# BatteryController.net
KiCad netlist of a schematic drawn in Altium Designer
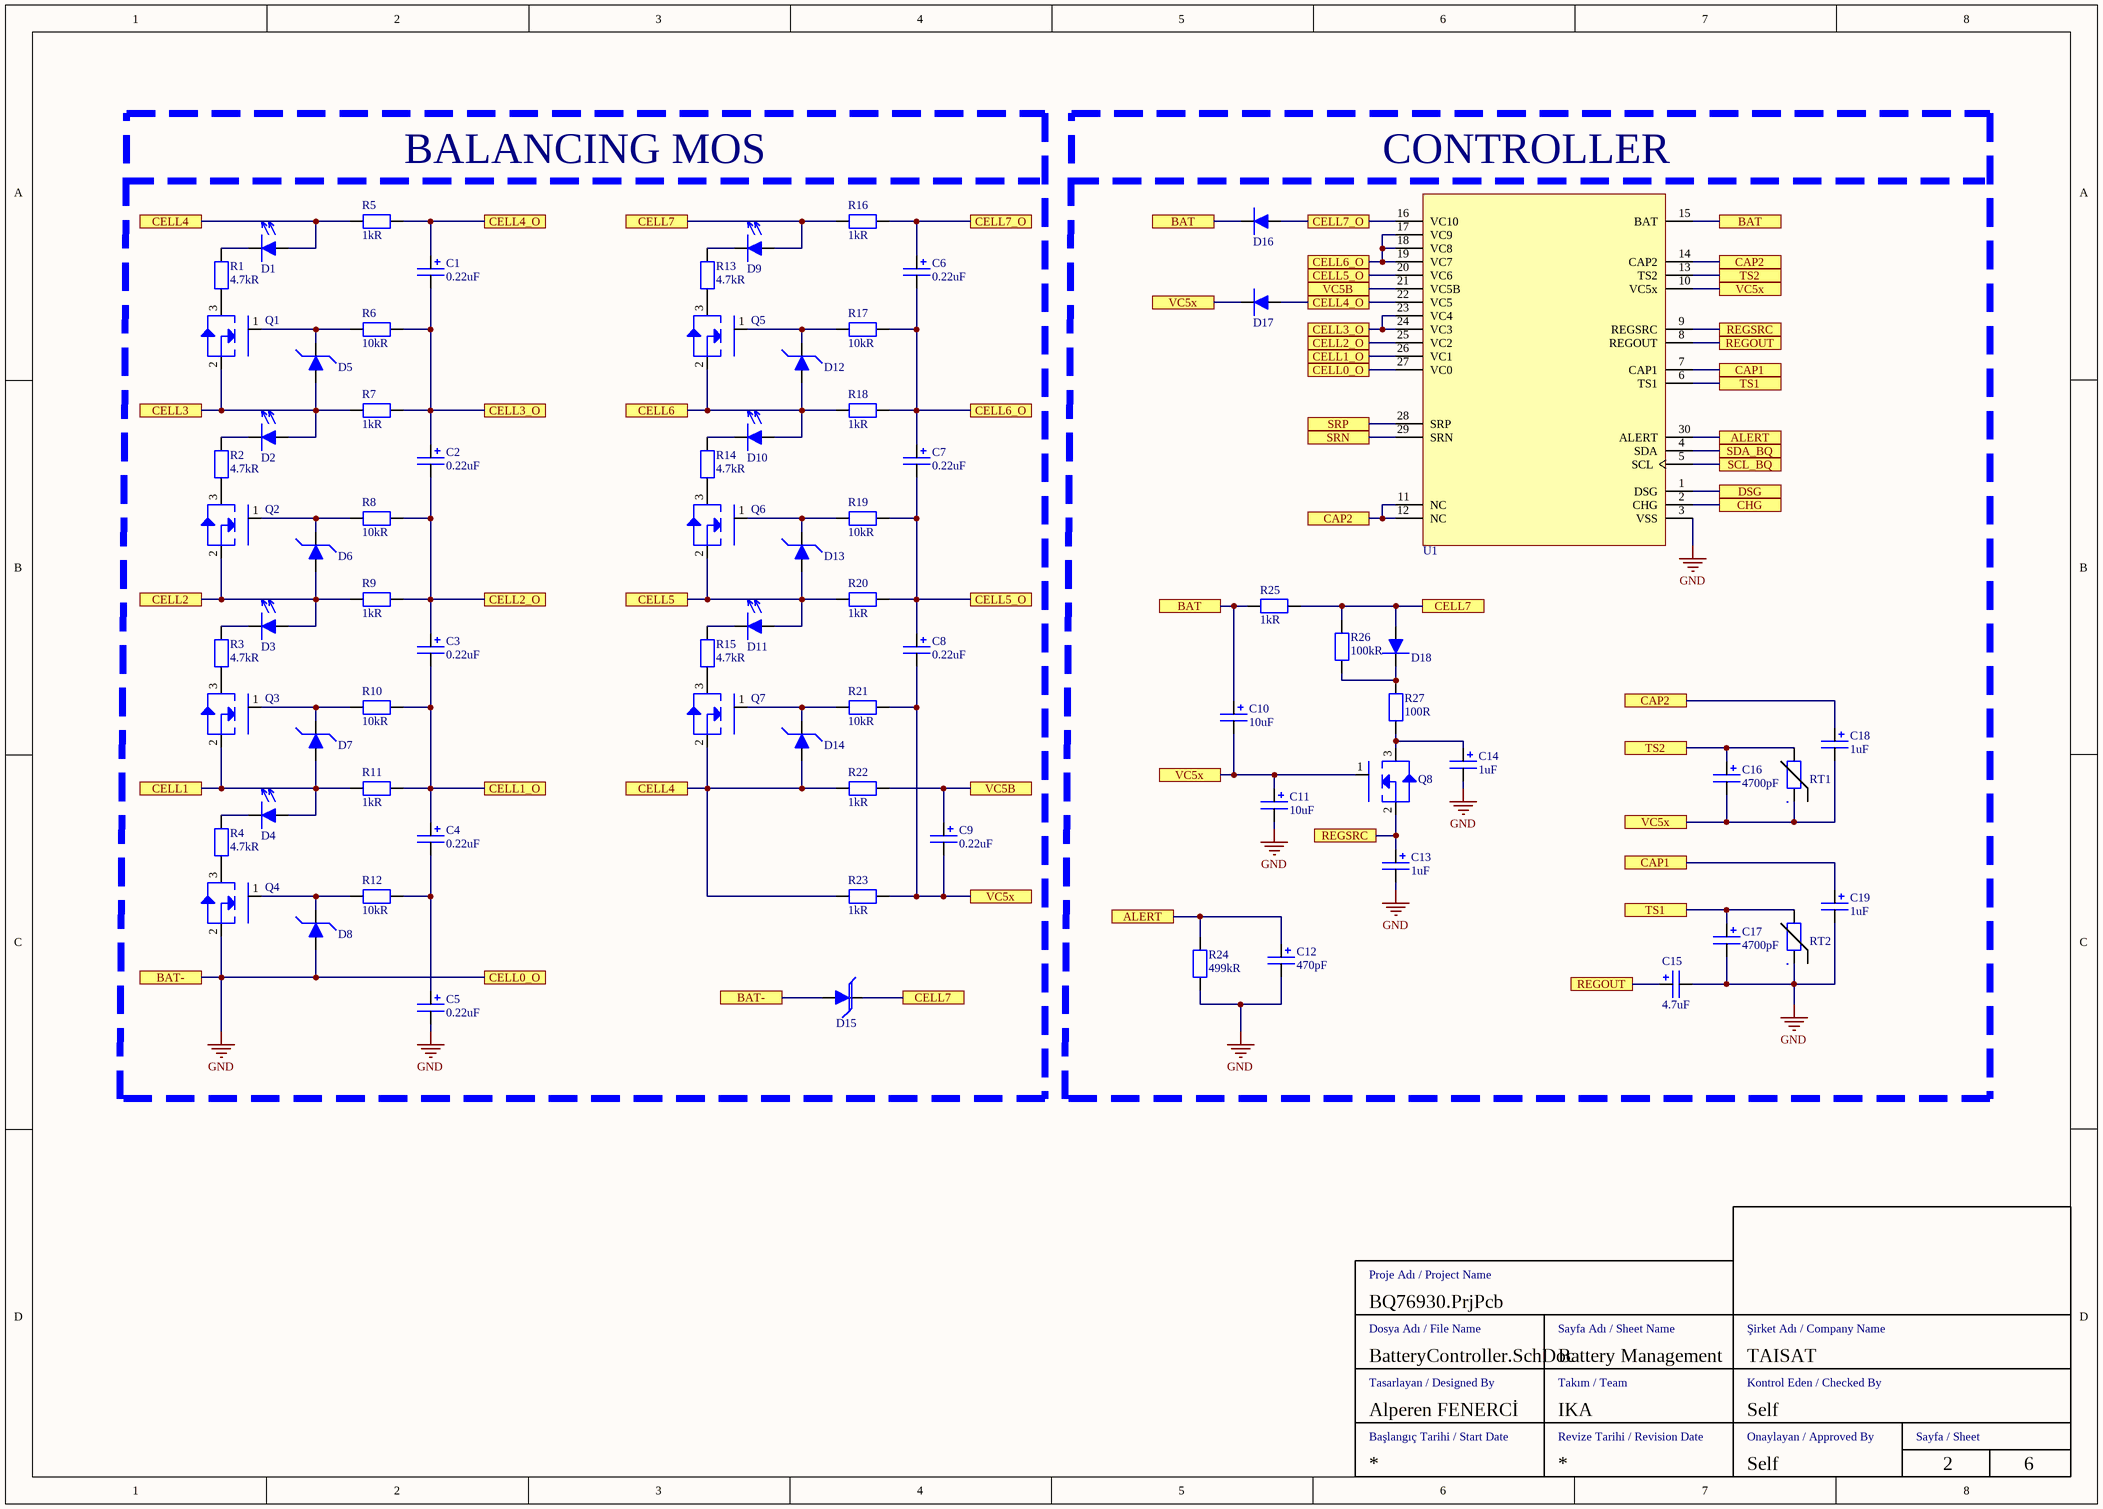
[diagram p0: BatteryController.SchDoc]

(export (version "E")
  (design (tool "Eeschema 10.0.6"))
  (components
    (comp (ref "C1")
      (value "0.22uF")
      (footprint "CAP 0603")
      (description "Multilayer Ceramic Capacitor")
      (fields (field (name "Comment") "CAP 0603"))
      (libsource (lib "Kaptanyums Lib") (part "CAP 0603"))
    )
    (comp (ref "C2")
      (value "0.22uF")
      (footprint "CAP 0603")
      (description "Multilayer Ceramic Capacitor")
      (fields (field (name "Comment") "CAP 0603"))
      (libsource (lib "Kaptanyums Lib") (part "CAP 0603"))
    )
    (comp (ref "C3")
      (value "0.22uF")
      (footprint "CAP 0603")
      (description "Multilayer Ceramic Capacitor")
      (fields (field (name "Comment") "CAP 0603"))
      (libsource (lib "Kaptanyums Lib") (part "CAP 0603"))
    )
    (comp (ref "C4")
      (value "0.22uF")
      (footprint "CAP 0603")
      (description "Multilayer Ceramic Capacitor")
      (fields (field (name "Comment") "CAP 0603"))
      (libsource (lib "Kaptanyums Lib") (part "CAP 0603"))
    )
    (comp (ref "C5")
      (value "0.22uF")
      (footprint "CAP 0603")
      (description "Multilayer Ceramic Capacitor")
      (fields (field (name "Comment") "CAP 0603"))
      (libsource (lib "Kaptanyums Lib") (part "CAP 0603"))
    )
    (comp (ref "C6")
      (value "0.22uF")
      (footprint "CAP 0603")
      (description "Multilayer Ceramic Capacitor")
      (fields (field (name "Comment") "CAP 0603"))
      (libsource (lib "Kaptanyums Lib") (part "CAP 0603"))
    )
    (comp (ref "C7")
      (value "0.22uF")
      (footprint "CAP 0603")
      (description "Multilayer Ceramic Capacitor")
      (fields (field (name "Comment") "CAP 0603"))
      (libsource (lib "Kaptanyums Lib") (part "CAP 0603"))
    )
    (comp (ref "C8")
      (value "0.22uF")
      (footprint "CAP 0603")
      (description "Multilayer Ceramic Capacitor")
      (fields (field (name "Comment") "CAP 0603"))
      (libsource (lib "Kaptanyums Lib") (part "CAP 0603"))
    )
    (comp (ref "C9")
      (value "0.22uF")
      (footprint "CAP 0603")
      (description "Multilayer Ceramic Capacitor")
      (fields (field (name "Comment") "CAP 0603"))
      (libsource (lib "Kaptanyums Lib") (part "CAP 0603"))
    )
    (comp (ref "C10")
      (value "10uF")
      (footprint "CAP 0603")
      (description "Multilayer Ceramic Capacitor")
      (fields (field (name "Comment") "CAP 0603"))
      (libsource (lib "Kaptanyums Lib") (part "CAP 0603"))
    )
    (comp (ref "C11")
      (value "10uF")
      (footprint "CAP 0603")
      (description "Multilayer Ceramic Capacitor")
      (fields (field (name "Comment") "CAP 0603"))
      (libsource (lib "Kaptanyums Lib") (part "CAP 0603"))
    )
    (comp (ref "C12")
      (value "470pF")
      (footprint "CAP 0603")
      (description "Multilayer Ceramic Capacitor")
      (fields (field (name "Comment") "CAP 0603"))
      (libsource (lib "Kaptanyums Lib") (part "CAP 0603"))
    )
    (comp (ref "C13")
      (value "1uF")
      (footprint "CAP 0603")
      (description "Multilayer Ceramic Capacitor")
      (fields (field (name "Comment") "CAP 0603"))
      (libsource (lib "Kaptanyums Lib") (part "CAP 0603"))
    )
    (comp (ref "C14")
      (value "1uF")
      (footprint "CAP 0603")
      (description "Multilayer Ceramic Capacitor")
      (fields (field (name "Comment") "CAP 0603"))
      (libsource (lib "Kaptanyums Lib") (part "CAP 0603"))
    )
    (comp (ref "C15")
      (value "4.7uF")
      (footprint "CAP 0603")
      (description "Multilayer Ceramic Capacitor")
      (fields (field (name "Comment") "CAP 0603"))
      (libsource (lib "Kaptanyums Lib") (part "CAP 0603"))
    )
    (comp (ref "C16")
      (value "4700pF")
      (footprint "CAP 0603")
      (description "Multilayer Ceramic Capacitor")
      (fields (field (name "Comment") "CAP 0603"))
      (libsource (lib "Kaptanyums Lib") (part "CAP 0603"))
    )
    (comp (ref "C17")
      (value "4700pF")
      (footprint "CAP 0603")
      (description "Multilayer Ceramic Capacitor")
      (fields (field (name "Comment") "CAP 0603"))
      (libsource (lib "Kaptanyums Lib") (part "CAP 0603"))
    )
    (comp (ref "C18")
      (value "1uF")
      (footprint "CAP 0603")
      (description "Multilayer Ceramic Capacitor")
      (fields (field (name "Comment") "CAP 0603"))
      (libsource (lib "Kaptanyums Lib") (part "CAP 0603"))
    )
    (comp (ref "C19")
      (value "1uF")
      (footprint "CAP 0603")
      (description "Multilayer Ceramic Capacitor")
      (fields (field (name "Comment") "CAP 0603"))
      (libsource (lib "Kaptanyums Lib") (part "CAP 0603"))
    )
    (comp (ref "D1")
      (value "LTW-C191TLA")
      (footprint "LED 0603")
      (description "Chip LED")
      (libsource (lib "Kaptanyums Lib") (part "LED 0603"))
    )
    (comp (ref "D2")
      (value "LTW-C191TLA")
      (footprint "LED 0603")
      (description "Chip LED")
      (libsource (lib "Kaptanyums Lib") (part "LED 0603"))
    )
    (comp (ref "D3")
      (value "LTW-C191TLA")
      (footprint "LED 0603")
      (description "Chip LED")
      (libsource (lib "Kaptanyums Lib") (part "LED 0603"))
    )
    (comp (ref "D4")
      (value "LTW-C191TLA")
      (footprint "LED 0603")
      (description "Chip LED")
      (libsource (lib "Kaptanyums Lib") (part "LED 0603"))
    )
    (comp (ref "D5")
      (value "MM3Z5V1T1G")
      (footprint "SOD323")
      (description "Diode Zener")
      (fields (field (name "VOLTAGE") "5.1V"))
      (libsource (lib "Kaptanyums Lib") (part "MM3Z5V1T1G"))
    )
    (comp (ref "D6")
      (value "MM3Z5V1T1G")
      (footprint "SOD323")
      (description "Diode Zener")
      (fields (field (name "VOLTAGE") "5.1V"))
      (libsource (lib "Kaptanyums Lib") (part "MM3Z5V1T1G"))
    )
    (comp (ref "D7")
      (value "MM3Z5V1T1G")
      (footprint "SOD323")
      (description "Diode Zener")
      (fields (field (name "VOLTAGE") "5.1V"))
      (libsource (lib "Kaptanyums Lib") (part "MM3Z5V1T1G"))
    )
    (comp (ref "D8")
      (value "MM3Z5V1T1G")
      (footprint "SOD323")
      (description "Diode Zener")
      (fields (field (name "VOLTAGE") "5.1V"))
      (libsource (lib "Kaptanyums Lib") (part "MM3Z5V1T1G"))
    )
    (comp (ref "D9")
      (value "LTW-C191TLA")
      (footprint "LED 0603")
      (description "Chip LED")
      (libsource (lib "Kaptanyums Lib") (part "LED 0603"))
    )
    (comp (ref "D10")
      (value "LTW-C191TLA")
      (footprint "LED 0603")
      (description "Chip LED")
      (libsource (lib "Kaptanyums Lib") (part "LED 0603"))
    )
    (comp (ref "D11")
      (value "LTW-C191TLA")
      (footprint "LED 0603")
      (description "Chip LED")
      (libsource (lib "Kaptanyums Lib") (part "LED 0603"))
    )
    (comp (ref "D12")
      (value "MM3Z5V1T1G")
      (footprint "SOD323")
      (description "Diode Zener")
      (fields (field (name "VOLTAGE") "5.1V"))
      (libsource (lib "Kaptanyums Lib") (part "MM3Z5V1T1G"))
    )
    (comp (ref "D13")
      (value "MM3Z5V1T1G")
      (footprint "SOD323")
      (description "Diode Zener")
      (fields (field (name "VOLTAGE") "5.1V"))
      (libsource (lib "Kaptanyums Lib") (part "MM3Z5V1T1G"))
    )
    (comp (ref "D14")
      (value "MM3Z5V1T1G")
      (footprint "SOD323")
      (description "Diode Zener")
      (fields (field (name "VOLTAGE") "5.1V"))
      (libsource (lib "Kaptanyums Lib") (part "MM3Z5V1T1G"))
    )
    (comp (ref "D15")
      (value "SMAJ36A-HT")
      (footprint "DO214AC")
      (description "Diode TVS")
      (fields (field (name "VOLTAGE") "36V"))
      (libsource (lib "Kaptanyums Lib") (part "SMAJ36A-HT"))
    )
    (comp (ref "D16")
      (value "BAV20W-7-F")
      (footprint "SOD123")
      (description "Diode Switch")
      (fields (field (name "VOLTAGE") "150V"))
      (libsource (lib "Kaptanyums Lib") (part "BAV20W-7-F"))
    )
    (comp (ref "D17")
      (value "BAV20W-7-F")
      (footprint "SOD123")
      (description "Diode Switch")
      (fields (field (name "VOLTAGE") "150V"))
      (libsource (lib "Kaptanyums Lib") (part "BAV20W-7-F"))
    )
    (comp (ref "D18")
      (value "1N4148WS")
      (footprint "SOD323")
      (description "Diode Gen")
      (fields (field (name "VOLTAGE") "75V"))
      (libsource (lib "Kaptanyums Lib") (part "1N4148WS"))
    )
    (comp (ref "Q1")
      (value "2N7002K")
      (footprint "SOT23-3")
      (description "MOSFET")
      (fields (field (name "VOLTAGE") "60V"))
      (libsource (lib "Kaptanyums Lib") (part "2N7002K"))
    )
    (comp (ref "Q2")
      (value "2N7002K")
      (footprint "SOT23-3")
      (description "MOSFET")
      (fields (field (name "VOLTAGE") "60V"))
      (libsource (lib "Kaptanyums Lib") (part "2N7002K"))
    )
    (comp (ref "Q3")
      (value "2N7002K")
      (footprint "SOT23-3")
      (description "MOSFET")
      (fields (field (name "VOLTAGE") "60V"))
      (libsource (lib "Kaptanyums Lib") (part "2N7002K"))
    )
    (comp (ref "Q4")
      (value "2N7002K")
      (footprint "SOT23-3")
      (description "MOSFET")
      (fields (field (name "VOLTAGE") "60V"))
      (libsource (lib "Kaptanyums Lib") (part "2N7002K"))
    )
    (comp (ref "Q5")
      (value "2N7002K")
      (footprint "SOT23-3")
      (description "MOSFET")
      (fields (field (name "VOLTAGE") "60V"))
      (libsource (lib "Kaptanyums Lib") (part "2N7002K"))
    )
    (comp (ref "Q6")
      (value "2N7002K")
      (footprint "SOT23-3")
      (description "MOSFET")
      (fields (field (name "VOLTAGE") "60V"))
      (libsource (lib "Kaptanyums Lib") (part "2N7002K"))
    )
    (comp (ref "Q7")
      (value "2N7002K")
      (footprint "SOT23-3")
      (description "MOSFET")
      (fields (field (name "VOLTAGE") "60V"))
      (libsource (lib "Kaptanyums Lib") (part "2N7002K"))
    )
    (comp (ref "Q8")
      (value "2N7002K")
      (footprint "SOT23-3")
      (description "MOSFET")
      (fields (field (name "VOLTAGE") "60V"))
      (libsource (lib "Kaptanyums Lib") (part "2N7002K"))
    )
    (comp (ref "R1")
      (value "4.7kR")
      (footprint "RESISTOR 1206")
      (description "SMD Chip Resistor")
      (fields (field (name "Comment") "RES 1206"))
      (libsource (lib "Kaptanyums Lib") (part "RES 1206"))
    )
    (comp (ref "R2")
      (value "4.7kR")
      (footprint "RESISTOR 1206")
      (description "SMD Chip Resistor")
      (fields (field (name "Comment") "RES 1206"))
      (libsource (lib "Kaptanyums Lib") (part "RES 1206"))
    )
    (comp (ref "R3")
      (value "4.7kR")
      (footprint "RESISTOR 1206")
      (description "SMD Chip Resistor")
      (fields (field (name "Comment") "RES 1206"))
      (libsource (lib "Kaptanyums Lib") (part "RES 1206"))
    )
    (comp (ref "R4")
      (value "4.7kR")
      (footprint "RESISTOR 1206")
      (description "SMD Chip Resistor")
      (fields (field (name "Comment") "RES 1206"))
      (libsource (lib "Kaptanyums Lib") (part "RES 1206"))
    )
    (comp (ref "R5")
      (value "1kR")
      (footprint "RESISTOR 0603")
      (description "SMD Chip Resistor")
      (fields (field (name "Comment") "RES 0603"))
      (libsource (lib "Kaptanyums Lib") (part "RES 0603"))
    )
    (comp (ref "R6")
      (value "10kR")
      (footprint "RESISTOR 0603")
      (description "SMD Chip Resistor")
      (fields (field (name "Comment") "RES 0603"))
      (libsource (lib "Kaptanyums Lib") (part "RES 0603"))
    )
    (comp (ref "R7")
      (value "1kR")
      (footprint "RESISTOR 0603")
      (description "SMD Chip Resistor")
      (fields (field (name "Comment") "RES 0603"))
      (libsource (lib "Kaptanyums Lib") (part "RES 0603"))
    )
    (comp (ref "R8")
      (value "10kR")
      (footprint "RESISTOR 0603")
      (description "SMD Chip Resistor")
      (fields (field (name "Comment") "RES 0603"))
      (libsource (lib "Kaptanyums Lib") (part "RES 0603"))
    )
    (comp (ref "R9")
      (value "1kR")
      (footprint "RESISTOR 0603")
      (description "SMD Chip Resistor")
      (fields (field (name "Comment") "RES 0603"))
      (libsource (lib "Kaptanyums Lib") (part "RES 0603"))
    )
    (comp (ref "R10")
      (value "10kR")
      (footprint "RESISTOR 0603")
      (description "SMD Chip Resistor")
      (fields (field (name "Comment") "RES 0603"))
      (libsource (lib "Kaptanyums Lib") (part "RES 0603"))
    )
    (comp (ref "R11")
      (value "1kR")
      (footprint "RESISTOR 0603")
      (description "SMD Chip Resistor")
      (fields (field (name "Comment") "RES 0603"))
      (libsource (lib "Kaptanyums Lib") (part "RES 0603"))
    )
    (comp (ref "R12")
      (value "10kR")
      (footprint "RESISTOR 0603")
      (description "SMD Chip Resistor")
      (fields (field (name "Comment") "RES 0603"))
      (libsource (lib "Kaptanyums Lib") (part "RES 0603"))
    )
    (comp (ref "R13")
      (value "4.7kR")
      (footprint "RESISTOR 1206")
      (description "SMD Chip Resistor")
      (fields (field (name "Comment") "RES 1206"))
      (libsource (lib "Kaptanyums Lib") (part "RES 1206"))
    )
    (comp (ref "R14")
      (value "4.7kR")
      (footprint "RESISTOR 1206")
      (description "SMD Chip Resistor")
      (fields (field (name "Comment") "RES 1206"))
      (libsource (lib "Kaptanyums Lib") (part "RES 1206"))
    )
    (comp (ref "R15")
      (value "4.7kR")
      (footprint "RESISTOR 1206")
      (description "SMD Chip Resistor")
      (fields (field (name "Comment") "RES 1206"))
      (libsource (lib "Kaptanyums Lib") (part "RES 1206"))
    )
    (comp (ref "R16")
      (value "1kR")
      (footprint "RESISTOR 0603")
      (description "SMD Chip Resistor")
      (fields (field (name "Comment") "RES 0603"))
      (libsource (lib "Kaptanyums Lib") (part "RES 0603"))
    )
    (comp (ref "R17")
      (value "10kR")
      (footprint "RESISTOR 0603")
      (description "SMD Chip Resistor")
      (fields (field (name "Comment") "RES 0603"))
      (libsource (lib "Kaptanyums Lib") (part "RES 0603"))
    )
    (comp (ref "R18")
      (value "1kR")
      (footprint "RESISTOR 0603")
      (description "SMD Chip Resistor")
      (fields (field (name "Comment") "RES 0603"))
      (libsource (lib "Kaptanyums Lib") (part "RES 0603"))
    )
    (comp (ref "R19")
      (value "10kR")
      (footprint "RESISTOR 0603")
      (description "SMD Chip Resistor")
      (fields (field (name "Comment") "RES 0603"))
      (libsource (lib "Kaptanyums Lib") (part "RES 0603"))
    )
    (comp (ref "R20")
      (value "1kR")
      (footprint "RESISTOR 0603")
      (description "SMD Chip Resistor")
      (fields (field (name "Comment") "RES 0603"))
      (libsource (lib "Kaptanyums Lib") (part "RES 0603"))
    )
    (comp (ref "R21")
      (value "10kR")
      (footprint "RESISTOR 0603")
      (description "SMD Chip Resistor")
      (fields (field (name "Comment") "RES 0603"))
      (libsource (lib "Kaptanyums Lib") (part "RES 0603"))
    )
    (comp (ref "R22")
      (value "1kR")
      (footprint "RESISTOR 0603")
      (description "SMD Chip Resistor")
      (fields (field (name "Comment") "RES 0603"))
      (libsource (lib "Kaptanyums Lib") (part "RES 0603"))
    )
    (comp (ref "R23")
      (value "1kR")
      (footprint "RESISTOR 0603")
      (description "SMD Chip Resistor")
      (fields (field (name "Comment") "RES 0603"))
      (libsource (lib "Kaptanyums Lib") (part "RES 0603"))
    )
    (comp (ref "R24")
      (value "499kR")
      (footprint "RESISTOR 0603")
      (description "SMD Chip Resistor")
      (fields (field (name "Comment") "RES 0603"))
      (libsource (lib "Kaptanyums Lib") (part "RES 0603"))
    )
    (comp (ref "R25")
      (value "1kR")
      (footprint "RESISTOR 0603")
      (description "SMD Chip Resistor")
      (fields (field (name "Comment") "RES 0603"))
      (libsource (lib "Kaptanyums Lib") (part "RES 0603"))
    )
    (comp (ref "R26")
      (value "100kR")
      (footprint "RESISTOR 0603")
      (description "SMD Chip Resistor")
      (fields (field (name "Comment") "RES 0603"))
      (libsource (lib "Kaptanyums Lib") (part "RES 0603"))
    )
    (comp (ref "R27")
      (value "100R")
      (footprint "RESISTOR 0603")
      (description "SMD Chip Resistor")
      (fields (field (name "Comment") "RES 0603"))
      (libsource (lib "Kaptanyums Lib") (part "RES 0603"))
    )
    (comp (ref "RT1")
      (value "NTC 0603")
      (footprint "NTC 0603")
      (description "Thermistor NTC")
      (libsource (lib "Kaptanyums Lib") (part "NTC 0603"))
    )
    (comp (ref "RT2")
      (value "NTC 0603")
      (footprint "NTC 0603")
      (description "Thermistor NTC")
      (libsource (lib "Kaptanyums Lib") (part "NTC 0603"))
    )
    (comp (ref "U1")
      (value "BQ76930")
      (footprint "TSSOP-30")
      (description "Cell Balance, Cell Monitoring")
      (libsource (lib "Kaptanyums Lib") (part "BQ76930"))
    )
  )
  (nets
    (net (code "1") (name "/ALERT") (class "Default")
      (node (ref "C12") (pin "1") (pinfunction "1_1") (pintype "passive"))
      (node (ref "R24") (pin "2") (pinfunction "2_2") (pintype "passive"))
      (node (ref "U1") (pin "30") (pinfunction "ALERT_30") (pintype "passive"))
    )
    (net (code "2") (name "/BAT") (class "Default")
      (node (ref "C10") (pin "1") (pinfunction "1_1") (pintype "passive"))
      (node (ref "D16") (pin "1") (pinfunction "1_1") (pintype "passive"))
      (node (ref "R25") (pin "2") (pinfunction "2_2") (pintype "passive"))
      (node (ref "U1") (pin "15") (pinfunction "BAT_15") (pintype "passive"))
    )
    (net (code "3") (name "/CAP1") (class "Default")
      (node (ref "C19") (pin "1") (pinfunction "1_1") (pintype "passive"))
      (node (ref "U1") (pin "7") (pinfunction "CAP1_7") (pintype "passive"))
    )
    (net (code "4") (name "/CAP2") (class "Default")
      (node (ref "C18") (pin "1") (pinfunction "1_1") (pintype "passive"))
      (node (ref "U1") (pin "11") (pinfunction "NC_11") (pintype "passive"))
      (node (ref "U1") (pin "12") (pinfunction "NC_12") (pintype "passive"))
      (node (ref "U1") (pin "14") (pinfunction "CAP2_14") (pintype "passive"))
    )
    (net (code "5") (name "/CELL1") (class "Default")
      (node (ref "D4") (pin "2") (pinfunction "2_2") (pintype "passive"))
      (node (ref "D7") (pin "2") (pinfunction "2_2") (pintype "passive"))
      (node (ref "Q3") (pin "2") (pinfunction "S_2") (pintype "passive"))
      (node (ref "R11") (pin "2") (pinfunction "2_2") (pintype "passive"))
    )
    (net (code "6") (name "/CELL1_O") (class "Default")
      (node (ref "C3") (pin "2") (pinfunction "2_2") (pintype "passive"))
      (node (ref "C4") (pin "1") (pinfunction "1_1") (pintype "passive"))
      (node (ref "R10") (pin "1") (pinfunction "1_1") (pintype "passive"))
      (node (ref "R11") (pin "1") (pinfunction "1_1") (pintype "passive"))
      (node (ref "U1") (pin "26") (pinfunction "VC1_26") (pintype "passive"))
    )
    (net (code "7") (name "/CELL2") (class "Default")
      (node (ref "D3") (pin "2") (pinfunction "2_2") (pintype "passive"))
      (node (ref "D6") (pin "2") (pinfunction "2_2") (pintype "passive"))
      (node (ref "Q2") (pin "2") (pinfunction "S_2") (pintype "passive"))
      (node (ref "R9") (pin "2") (pinfunction "2_2") (pintype "passive"))
    )
    (net (code "8") (name "/CELL2_O") (class "Default")
      (node (ref "C2") (pin "2") (pinfunction "2_2") (pintype "passive"))
      (node (ref "C3") (pin "1") (pinfunction "1_1") (pintype "passive"))
      (node (ref "R8") (pin "1") (pinfunction "1_1") (pintype "passive"))
      (node (ref "R9") (pin "1") (pinfunction "1_1") (pintype "passive"))
      (node (ref "U1") (pin "25") (pinfunction "VC2_25") (pintype "passive"))
    )
    (net (code "9") (name "/CELL3") (class "Default")
      (node (ref "D2") (pin "2") (pinfunction "2_2") (pintype "passive"))
      (node (ref "D5") (pin "2") (pinfunction "2_2") (pintype "passive"))
      (node (ref "Q1") (pin "2") (pinfunction "S_2") (pintype "passive"))
      (node (ref "R7") (pin "2") (pinfunction "2_2") (pintype "passive"))
    )
    (net (code "10") (name "/CELL3_O") (class "Default")
      (node (ref "C1") (pin "2") (pinfunction "2_2") (pintype "passive"))
      (node (ref "C2") (pin "1") (pinfunction "1_1") (pintype "passive"))
      (node (ref "R6") (pin "1") (pinfunction "1_1") (pintype "passive"))
      (node (ref "R7") (pin "1") (pinfunction "1_1") (pintype "passive"))
      (node (ref "U1") (pin "23") (pinfunction "VC4_23") (pintype "passive"))
      (node (ref "U1") (pin "24") (pinfunction "VC3_24") (pintype "passive"))
    )
    (net (code "11") (name "/CELL4") (class "Default")
      (node (ref "D1") (pin "2") (pinfunction "2_2") (pintype "passive"))
      (node (ref "D14") (pin "2") (pinfunction "2_2") (pintype "passive"))
      (node (ref "Q7") (pin "2") (pinfunction "S_2") (pintype "passive"))
      (node (ref "R22") (pin "2") (pinfunction "2_2") (pintype "passive"))
      (node (ref "R23") (pin "2") (pinfunction "2_2") (pintype "passive"))
      (node (ref "R5") (pin "2") (pinfunction "2_2") (pintype "passive"))
    )
    (net (code "12") (name "/CELL4_O") (class "Default")
      (node (ref "C1") (pin "1") (pinfunction "1_1") (pintype "passive"))
      (node (ref "D17") (pin "2") (pinfunction "2_2") (pintype "passive"))
      (node (ref "R5") (pin "1") (pinfunction "1_1") (pintype "passive"))
      (node (ref "U1") (pin "22") (pinfunction "VC5_22") (pintype "passive"))
    )
    (net (code "13") (name "/CELL5") (class "Default")
      (node (ref "D11") (pin "2") (pinfunction "2_2") (pintype "passive"))
      (node (ref "D13") (pin "2") (pinfunction "2_2") (pintype "passive"))
      (node (ref "Q6") (pin "2") (pinfunction "S_2") (pintype "passive"))
      (node (ref "R20") (pin "2") (pinfunction "2_2") (pintype "passive"))
    )
    (net (code "14") (name "/CELL5_O") (class "Default")
      (node (ref "C7") (pin "2") (pinfunction "2_2") (pintype "passive"))
      (node (ref "C8") (pin "1") (pinfunction "1_1") (pintype "passive"))
      (node (ref "R19") (pin "1") (pinfunction "1_1") (pintype "passive"))
      (node (ref "R20") (pin "1") (pinfunction "1_1") (pintype "passive"))
      (node (ref "U1") (pin "20") (pinfunction "VC6_20") (pintype "passive"))
    )
    (net (code "15") (name "/CELL6") (class "Default")
      (node (ref "D10") (pin "2") (pinfunction "2_2") (pintype "passive"))
      (node (ref "D12") (pin "2") (pinfunction "2_2") (pintype "passive"))
      (node (ref "Q5") (pin "2") (pinfunction "S_2") (pintype "passive"))
      (node (ref "R18") (pin "2") (pinfunction "2_2") (pintype "passive"))
    )
    (net (code "16") (name "/CELL6_O") (class "Default")
      (node (ref "C6") (pin "2") (pinfunction "2_2") (pintype "passive"))
      (node (ref "C7") (pin "1") (pinfunction "1_1") (pintype "passive"))
      (node (ref "R17") (pin "1") (pinfunction "1_1") (pintype "passive"))
      (node (ref "R18") (pin "1") (pinfunction "1_1") (pintype "passive"))
      (node (ref "U1") (pin "17") (pinfunction "VC9_17") (pintype "passive"))
      (node (ref "U1") (pin "18") (pinfunction "VC8_18") (pintype "passive"))
      (node (ref "U1") (pin "19") (pinfunction "VC7_19") (pintype "passive"))
    )
    (net (code "17") (name "/CELL7") (class "Default")
      (node (ref "D15") (pin "1") (pinfunction "1_1") (pintype "passive"))
      (node (ref "D18") (pin "2") (pinfunction "2_2") (pintype "passive"))
      (node (ref "D9") (pin "2") (pinfunction "2_2") (pintype "passive"))
      (node (ref "R16") (pin "2") (pinfunction "2_2") (pintype "passive"))
      (node (ref "R25") (pin "1") (pinfunction "1_1") (pintype "passive"))
      (node (ref "R26") (pin "2") (pinfunction "2_2") (pintype "passive"))
    )
    (net (code "18") (name "/CELL7_O") (class "Default")
      (node (ref "C6") (pin "1") (pinfunction "1_1") (pintype "passive"))
      (node (ref "D16") (pin "2") (pinfunction "2_2") (pintype "passive"))
      (node (ref "R16") (pin "1") (pinfunction "1_1") (pintype "passive"))
      (node (ref "U1") (pin "16") (pinfunction "VC10_16") (pintype "passive"))
    )
    (net (code "19") (name "/CHG") (class "Default")
      (node (ref "U1") (pin "2") (pinfunction "CHG_2") (pintype "passive"))
    )
    (net (code "20") (name "/DSG") (class "Default")
      (node (ref "U1") (pin "1") (pinfunction "DSG_1") (pintype "passive"))
    )
    (net (code "21") (name "/REGOUT") (class "Default")
      (node (ref "C15") (pin "1") (pinfunction "1_1") (pintype "passive"))
      (node (ref "U1") (pin "8") (pinfunction "REGOUT_8") (pintype "passive"))
    )
    (net (code "22") (name "/REGSRC") (class "Default")
      (node (ref "C13") (pin "1") (pinfunction "1_1") (pintype "passive"))
      (node (ref "Q8") (pin "2") (pinfunction "S_2") (pintype "passive"))
      (node (ref "U1") (pin "9") (pinfunction "REGSRC_9") (pintype "passive"))
    )
    (net (code "23") (name "/SCL_BQ") (class "Default")
      (node (ref "U1") (pin "5") (pinfunction "SCL_5") (pintype "passive"))
    )
    (net (code "24") (name "/SDA_BQ") (class "Default")
      (node (ref "U1") (pin "4") (pinfunction "SDA_4") (pintype "passive"))
    )
    (net (code "25") (name "/SRN") (class "Default")
      (node (ref "U1") (pin "29") (pinfunction "SRN_29") (pintype "passive"))
    )
    (net (code "26") (name "/SRP") (class "Default")
      (node (ref "U1") (pin "28") (pinfunction "SRP_28") (pintype "passive"))
    )
    (net (code "27") (name "/TS1") (class "Default")
      (node (ref "C17") (pin "1") (pinfunction "1_1") (pintype "passive"))
      (node (ref "RT2") (pin "2") (pinfunction "2_2") (pintype "passive"))
      (node (ref "U1") (pin "6") (pinfunction "TS1_6") (pintype "passive"))
    )
    (net (code "28") (name "/TS2") (class "Default")
      (node (ref "C16") (pin "1") (pinfunction "1_1") (pintype "passive"))
      (node (ref "RT1") (pin "2") (pinfunction "2_2") (pintype "passive"))
      (node (ref "U1") (pin "13") (pinfunction "TS2_13") (pintype "passive"))
    )
    (net (code "29") (name "/VC5B") (class "Default")
      (node (ref "C9") (pin "1") (pinfunction "1_1") (pintype "passive"))
      (node (ref "R22") (pin "1") (pinfunction "1_1") (pintype "passive"))
      (node (ref "U1") (pin "21") (pinfunction "VC5B_21") (pintype "passive"))
    )
    (net (code "30") (name "/VC5x") (class "Default")
      (node (ref "C10") (pin "2") (pinfunction "2_2") (pintype "passive"))
      (node (ref "C11") (pin "1") (pinfunction "1_1") (pintype "passive"))
      (node (ref "C16") (pin "2") (pinfunction "2_2") (pintype "passive"))
      (node (ref "C18") (pin "2") (pinfunction "2_2") (pintype "passive"))
      (node (ref "C8") (pin "2") (pinfunction "2_2") (pintype "passive"))
      (node (ref "C9") (pin "2") (pinfunction "2_2") (pintype "passive"))
      (node (ref "D17") (pin "1") (pinfunction "1_1") (pintype "passive"))
      (node (ref "Q8") (pin "1") (pinfunction "G_1") (pintype "passive"))
      (node (ref "R21") (pin "1") (pinfunction "1_1") (pintype "passive"))
      (node (ref "R23") (pin "1") (pinfunction "1_1") (pintype "passive"))
      (node (ref "RT1") (pin "1") (pinfunction "1_1") (pintype "passive"))
      (node (ref "U1") (pin "10") (pinfunction "VC5x_10") (pintype "passive"))
    )
    (net (code "31") (name "GND") (class "Default")
      (node (ref "C11") (pin "2") (pinfunction "2_2") (pintype "passive"))
      (node (ref "C12") (pin "2") (pinfunction "2_2") (pintype "passive"))
      (node (ref "C13") (pin "2") (pinfunction "2_2") (pintype "passive"))
      (node (ref "C14") (pin "2") (pinfunction "2_2") (pintype "passive"))
      (node (ref "C15") (pin "2") (pinfunction "2_2") (pintype "passive"))
      (node (ref "C17") (pin "2") (pinfunction "2_2") (pintype "passive"))
      (node (ref "C19") (pin "2") (pinfunction "2_2") (pintype "passive"))
      (node (ref "C5") (pin "2") (pinfunction "2_2") (pintype "passive"))
      (node (ref "D15") (pin "2") (pinfunction "2_2") (pintype "passive"))
      (node (ref "D8") (pin "2") (pinfunction "2_2") (pintype "passive"))
      (node (ref "Q4") (pin "2") (pinfunction "S_2") (pintype "passive"))
      (node (ref "R24") (pin "1") (pinfunction "1_1") (pintype "passive"))
      (node (ref "RT2") (pin "1") (pinfunction "1_1") (pintype "passive"))
      (node (ref "U1") (pin "27") (pinfunction "VC0_27") (pintype "passive"))
      (node (ref "U1") (pin "3") (pinfunction "VSS_3") (pintype "passive"))
    )
    (net (code "32") (name "Net-(C4-Pad2)") (class "Default")
      (node (ref "C4") (pin "2") (pinfunction "2_2") (pintype "passive"))
      (node (ref "C5") (pin "1") (pinfunction "1_1") (pintype "passive"))
      (node (ref "R12") (pin "1") (pinfunction "1_1") (pintype "passive"))
    )
    (net (code "33") (name "Net-(D1-Pad1)") (class "Default")
      (node (ref "D1") (pin "1") (pinfunction "1_1") (pintype "passive"))
      (node (ref "R1") (pin "2") (pinfunction "2_2") (pintype "passive"))
    )
    (net (code "34") (name "Net-(D2-Pad1)") (class "Default")
      (node (ref "D2") (pin "1") (pinfunction "1_1") (pintype "passive"))
      (node (ref "R2") (pin "2") (pinfunction "2_2") (pintype "passive"))
    )
    (net (code "35") (name "Net-(D3-Pad1)") (class "Default")
      (node (ref "D3") (pin "1") (pinfunction "1_1") (pintype "passive"))
      (node (ref "R3") (pin "2") (pinfunction "2_2") (pintype "passive"))
    )
    (net (code "36") (name "Net-(D4-Pad1)") (class "Default")
      (node (ref "D4") (pin "1") (pinfunction "1_1") (pintype "passive"))
      (node (ref "R4") (pin "2") (pinfunction "2_2") (pintype "passive"))
    )
    (net (code "37") (name "Net-(D9-Pad1)") (class "Default")
      (node (ref "D9") (pin "1") (pinfunction "1_1") (pintype "passive"))
      (node (ref "R13") (pin "2") (pinfunction "2_2") (pintype "passive"))
    )
    (net (code "38") (name "Net-(D10-Pad1)") (class "Default")
      (node (ref "D10") (pin "1") (pinfunction "1_1") (pintype "passive"))
      (node (ref "R14") (pin "2") (pinfunction "2_2") (pintype "passive"))
    )
    (net (code "39") (name "Net-(D11-Pad1)") (class "Default")
      (node (ref "D11") (pin "1") (pinfunction "1_1") (pintype "passive"))
      (node (ref "R15") (pin "2") (pinfunction "2_2") (pintype "passive"))
    )
    (net (code "40") (name "Net-(D18-Pad1)") (class "Default")
      (node (ref "D18") (pin "1") (pinfunction "1_1") (pintype "passive"))
      (node (ref "R26") (pin "1") (pinfunction "1_1") (pintype "passive"))
      (node (ref "R27") (pin "2") (pinfunction "2_2") (pintype "passive"))
    )
    (net (code "41") (name "Net-(Q1-D)") (class "Default")
      (node (ref "Q1") (pin "3") (pinfunction "D_3") (pintype "passive"))
      (node (ref "R1") (pin "1") (pinfunction "1_1") (pintype "passive"))
    )
    (net (code "42") (name "Net-(Q1-G)") (class "Default")
      (node (ref "D5") (pin "1") (pinfunction "1_1") (pintype "passive"))
      (node (ref "Q1") (pin "1") (pinfunction "G_1") (pintype "passive"))
      (node (ref "R6") (pin "2") (pinfunction "2_2") (pintype "passive"))
    )
    (net (code "43") (name "Net-(Q2-D)") (class "Default")
      (node (ref "Q2") (pin "3") (pinfunction "D_3") (pintype "passive"))
      (node (ref "R2") (pin "1") (pinfunction "1_1") (pintype "passive"))
    )
    (net (code "44") (name "Net-(Q2-G)") (class "Default")
      (node (ref "D6") (pin "1") (pinfunction "1_1") (pintype "passive"))
      (node (ref "Q2") (pin "1") (pinfunction "G_1") (pintype "passive"))
      (node (ref "R8") (pin "2") (pinfunction "2_2") (pintype "passive"))
    )
    (net (code "45") (name "Net-(Q3-D)") (class "Default")
      (node (ref "Q3") (pin "3") (pinfunction "D_3") (pintype "passive"))
      (node (ref "R3") (pin "1") (pinfunction "1_1") (pintype "passive"))
    )
    (net (code "46") (name "Net-(Q3-G)") (class "Default")
      (node (ref "D7") (pin "1") (pinfunction "1_1") (pintype "passive"))
      (node (ref "Q3") (pin "1") (pinfunction "G_1") (pintype "passive"))
      (node (ref "R10") (pin "2") (pinfunction "2_2") (pintype "passive"))
    )
    (net (code "47") (name "Net-(Q4-D)") (class "Default")
      (node (ref "Q4") (pin "3") (pinfunction "D_3") (pintype "passive"))
      (node (ref "R4") (pin "1") (pinfunction "1_1") (pintype "passive"))
    )
    (net (code "48") (name "Net-(Q4-G)") (class "Default")
      (node (ref "D8") (pin "1") (pinfunction "1_1") (pintype "passive"))
      (node (ref "Q4") (pin "1") (pinfunction "G_1") (pintype "passive"))
      (node (ref "R12") (pin "2") (pinfunction "2_2") (pintype "passive"))
    )
    (net (code "49") (name "Net-(Q5-D)") (class "Default")
      (node (ref "Q5") (pin "3") (pinfunction "D_3") (pintype "passive"))
      (node (ref "R13") (pin "1") (pinfunction "1_1") (pintype "passive"))
    )
    (net (code "50") (name "Net-(Q5-G)") (class "Default")
      (node (ref "D12") (pin "1") (pinfunction "1_1") (pintype "passive"))
      (node (ref "Q5") (pin "1") (pinfunction "G_1") (pintype "passive"))
      (node (ref "R17") (pin "2") (pinfunction "2_2") (pintype "passive"))
    )
    (net (code "51") (name "Net-(Q6-D)") (class "Default")
      (node (ref "Q6") (pin "3") (pinfunction "D_3") (pintype "passive"))
      (node (ref "R14") (pin "1") (pinfunction "1_1") (pintype "passive"))
    )
    (net (code "52") (name "Net-(Q6-G)") (class "Default")
      (node (ref "D13") (pin "1") (pinfunction "1_1") (pintype "passive"))
      (node (ref "Q6") (pin "1") (pinfunction "G_1") (pintype "passive"))
      (node (ref "R19") (pin "2") (pinfunction "2_2") (pintype "passive"))
    )
    (net (code "53") (name "Net-(Q7-D)") (class "Default")
      (node (ref "Q7") (pin "3") (pinfunction "D_3") (pintype "passive"))
      (node (ref "R15") (pin "1") (pinfunction "1_1") (pintype "passive"))
    )
    (net (code "54") (name "Net-(Q7-G)") (class "Default")
      (node (ref "D14") (pin "1") (pinfunction "1_1") (pintype "passive"))
      (node (ref "Q7") (pin "1") (pinfunction "G_1") (pintype "passive"))
      (node (ref "R21") (pin "2") (pinfunction "2_2") (pintype "passive"))
    )
    (net (code "55") (name "Net-(Q8-D)") (class "Default")
      (node (ref "C14") (pin "1") (pinfunction "1_1") (pintype "passive"))
      (node (ref "Q8") (pin "3") (pinfunction "D_3") (pintype "passive"))
      (node (ref "R27") (pin "1") (pinfunction "1_1") (pintype "passive"))
    )
  )
)
